# Preamp2_schematic.net
KiCad netlist of a schematic drawn in Altium Designer
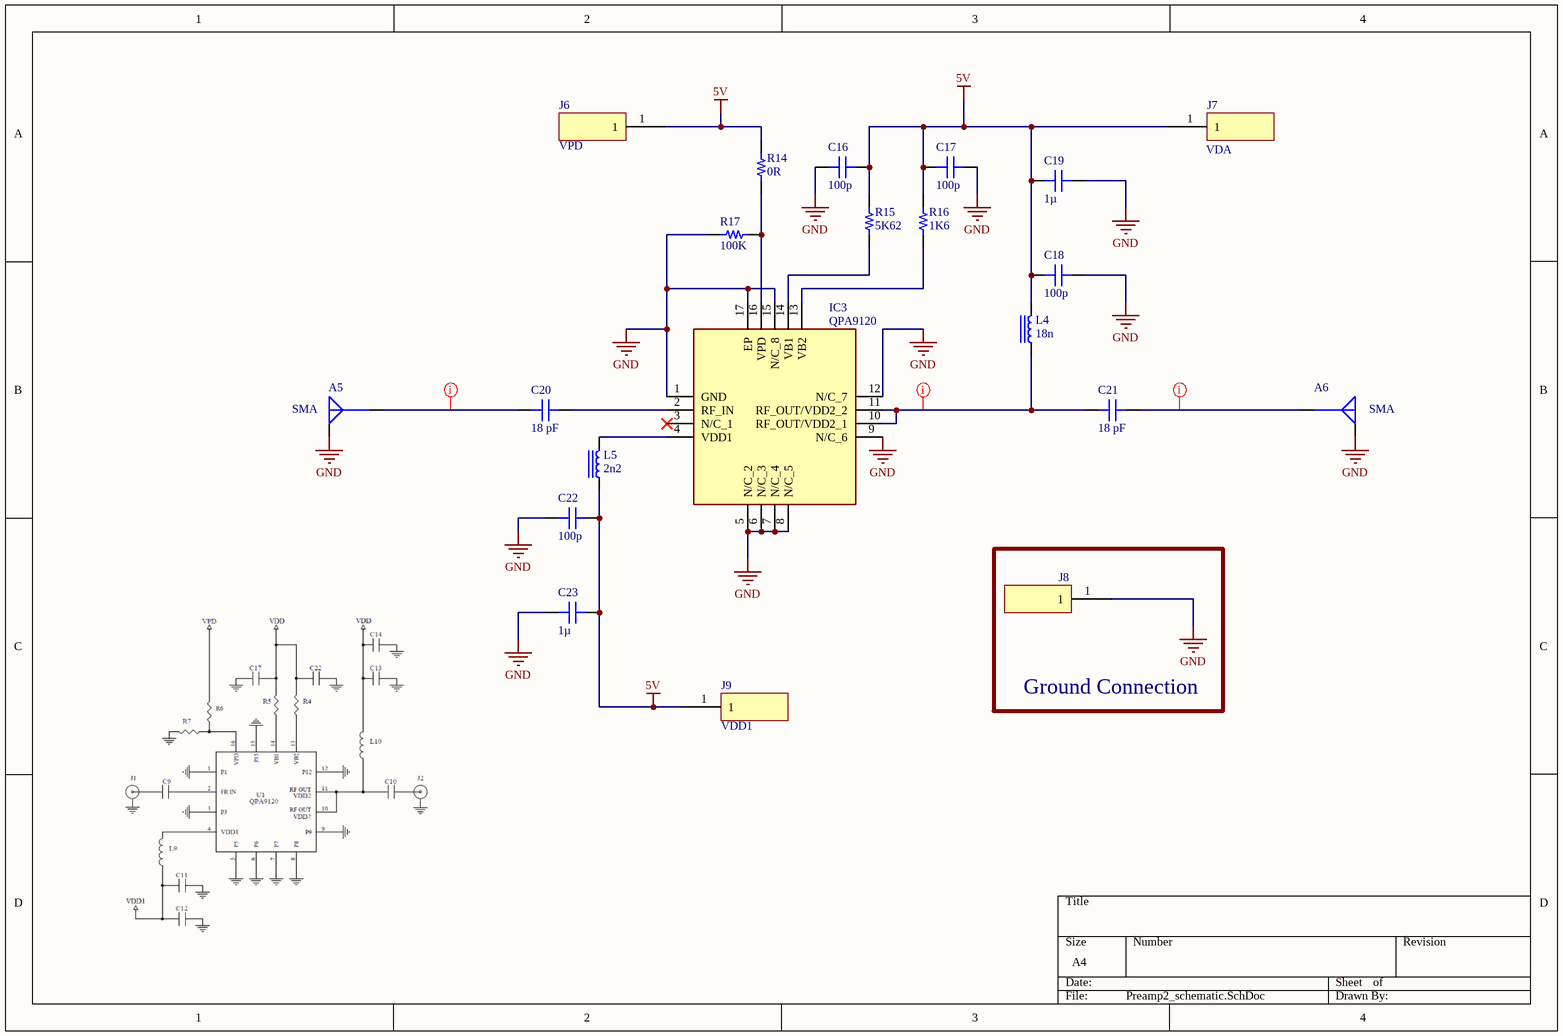
[diagram p0: Preamp2_schematic.SchDoc]

(export (version "E")
  (design (tool "Eeschema 10.0.6"))
  (components
    (comp (ref "A5")
      (value "0732511150")
      (footprint "MOLEX SD-73251-115")
      (description "CONN SMA RCPT STR 50OHM EDGE MNT")
      (fields (field (name "CONNECTOR STYLE") "SMA") (field (name "MANUFACTURER") "Molex"))
      (libsource (lib "Celestial Altium Library - altium_library") (part "Basic Antenna"))
    )
    (comp (ref "A6")
      (value "0732511150")
      (footprint "MOLEX SD-73251-115")
      (description "CONN SMA RCPT STR 50OHM EDGE MNT")
      (fields (field (name "CONNECTOR STYLE") "SMA") (field (name "MANUFACTURER") "Molex"))
      (libsource (lib "Celestial Altium Library - altium_library") (part "Basic Antenna"))
    )
    (comp (ref "C16")
      (value "100p")
      (footprint "CAP 0402_1005 RF")
      (description "CAP CER 100PF 25V C0G/NP0 0402")
      (fields (field (name "PART NUMBER") "CBR04C101J3GAC") (field (name "MANUFACTURER") "KEMET"))
      (libsource (lib "Celestial Altium Library - altium_library") (part "Capacitor"))
    )
    (comp (ref "C17")
      (value "100p")
      (footprint "CAP 0402_1005 RF")
      (description "CAP CER 100PF 25V C0G/NP0 0402")
      (fields (field (name "PART NUMBER") "CBR04C101J3GAC") (field (name "MANUFACTURER") "KEMET"))
      (libsource (lib "Celestial Altium Library - altium_library") (part "Capacitor"))
    )
    (comp (ref "C18")
      (value "100p")
      (footprint "CAP 0402_1005 RF")
      (description "CAP CER 100PF 25V C0G/NP0 0402")
      (fields (field (name "PART NUMBER") "CBR04C101J3GAC") (field (name "MANUFACTURER") "KEMET"))
      (libsource (lib "Celestial Altium Library - altium_library") (part "Capacitor"))
    )
    (comp (ref "C19")
      (value "1µ")
      (footprint "CAP 0603_1608")
      (description "CAP CER 1UF 25V X7R 0603")
      (fields
        (field (name "PART NUMBER") "GCM188R71E105KA64J")
        (field (name "MANUFACTURER") "Murata Electronics")
      )
      (libsource (lib "Celestial Altium Library - altium_library") (part "Capacitor"))
    )
    (comp (ref "C20")
      (value "18 pF")
      (footprint "CAP 0402_1005 RF")
      (description "CAP CER 18PF 200V NP0 0402")
      (fields
        (field (name "PART NUMBER") "600L180GT200T")
        (field (name "MANUFACTURER") "American Technical Ceramics")
      )
      (libsource (lib "Celestial Altium Library - altium_library") (part "Capacitor"))
    )
    (comp (ref "C21")
      (value "18 pF")
      (footprint "CAP 0402_1005 RF")
      (description "CAP CER 18PF 200V NP0 0402")
      (fields
        (field (name "PART NUMBER") "600L180GT200T")
        (field (name "MANUFACTURER") "American Technical Ceramics")
      )
      (libsource (lib "Celestial Altium Library - altium_library") (part "Capacitor"))
    )
    (comp (ref "C22")
      (value "100p")
      (footprint "CAP 0603_1608 RF")
      (description "CAP CER 100PF 250V NP0 0603")
      (fields
        (field (name "PART NUMBER") "600S101GW250XT")
        (field (name "MANUFACTURER") "American Technical Ceramics")
      )
      (libsource (lib "Celestial Altium Library - altium_library") (part "Capacitor"))
    )
    (comp (ref "C23")
      (value "1µ")
      (footprint "CAP 0603_1608")
      (description "CAP CER 1UF 25V X7R 0603")
      (fields
        (field (name "PART NUMBER") "GCM188R71E105KA64J")
        (field (name "MANUFACTURER") "Murata Electronics")
      )
      (libsource (lib "Celestial Altium Library - altium_library") (part "Capacitor"))
    )
    (comp (ref "IC3")
      (value "QPA9120")
      (footprint "SamacSys:QFN50P300X300X86-17N-D")
      (description "Integrated Circuit")
      (libsource (lib "SamacSys") (part "QPA9120"))
    )
    (comp (ref "J6")
      (value "Nail_Head")
      (footprint "Nail_Head")
      (description "1460-2-00-80-00-00-03-0 Mill-Max")
      (libsource (lib "") (part "Nail_Head_1"))
    )
    (comp (ref "J7")
      (value "Nail_Head")
      (footprint "Nail_Head")
      (description "1460-2-00-80-00-00-03-0 Mill-Max")
      (libsource (lib "ARIS_COM_Transponder") (part "Nail_Head"))
    )
    (comp (ref "J8")
      (value "Nail_Head")
      (footprint "Nail_Head")
      (description "1460-2-00-80-00-00-03-0 Mill-Max")
      (libsource (lib "") (part "Nail_Head_1"))
    )
    (comp (ref "J9")
      (value "Nail_Head")
      (footprint "Nail_Head")
      (description "1460-2-00-80-00-00-03-0 Mill-Max")
      (libsource (lib "ARIS_COM_Transponder") (part "Nail_Head"))
    )
    (comp (ref "L4")
      (value "18n")
      (footprint "IND 0402_1005 RF WW")
      (description "FIXED IND 18NH 1.05A 0.13OHM SMD")
      (fields
        (field (name "PART NUMBER") "LQW15AN18NG8ZD")
        (field (name "MANUFACTURER") "Murata Electronics")
      )
      (libsource (lib "Celestial Altium Library - altium_library") (part "Inductor"))
    )
    (comp (ref "L5")
      (value "2n2")
      (footprint "IND 0402_1005 RF WW")
      (description "FIXED IND 2.2NH 2.53A 0.022OHM")
      (fields
        (field (name "PART NUMBER") "LQW15AN2N2D8ZD")
        (field (name "MANUFACTURER") "Murata Electronics")
      )
      (libsource (lib "Celestial Altium Library - altium_library") (part "Inductor"))
    )
    (comp (ref "R14")
      (value "0R")
      (footprint "RES 0603_1608")
      (description "0603 26 AMP JUMPER")
      (fields (field (name "PART NUMBER") "JR0603X26E") (field (name "MANUFACTURER") "Ohmite"))
      (libsource (lib "Celestial Altium Library - altium_library") (part "Resistor"))
    )
    (comp (ref "R15")
      (value "5K62")
      (footprint "RES 0402_1005")
      (description "RES SMD 5.62K OHM 1% 1/16W 0402")
      (fields (field (name "PART NUMBER") "CRCW04025K62FKED") (field (name "MANUFACTURER") "Vishay Dale"))
      (libsource (lib "Celestial Altium Library - altium_library") (part "Resistor"))
    )
    (comp (ref "R16")
      (value "1K6")
      (footprint "RES 0402_1005")
      (description "RES SMD 1.6K OHM 1% 1/16W 0402")
      (fields (field (name "PART NUMBER") "CR0402-FX-1601GLF") (field (name "MANUFACTURER") "Bourns Inc."))
      (libsource (lib "Celestial Altium Library - altium_library") (part "Resistor"))
    )
    (comp (ref "R17")
      (value "100K")
      (footprint "RES 0402_1005")
      (description "RES SMD 100K OHM 1% 1/5W 0402")
      (fields (field (name "PART NUMBER") "CRCW0402100KFKEDHP") (field (name "MANUFACTURER") "Vishay Dale"))
      (libsource (lib "Celestial Altium Library - altium_library") (part "Resistor"))
    )
  )
  (nets
    (net (code "1") (name "5V") (class "Default")
      (node (ref "C16") (pin "2") (pinfunction "2_2") (pintype "passive"))
      (node (ref "C17") (pin "1") (pinfunction "1_1") (pintype "passive"))
      (node (ref "C18") (pin "1") (pinfunction "1_1") (pintype "passive"))
      (node (ref "C19") (pin "1") (pinfunction "1_1") (pintype "passive"))
      (node (ref "C22") (pin "2") (pinfunction "2_2") (pintype "passive"))
      (node (ref "C23") (pin "2") (pinfunction "2_2") (pintype "passive"))
      (node (ref "J6") (pin "1") (pinfunction "1_1") (pintype "passive"))
      (node (ref "J7") (pin "1") (pinfunction "1_1") (pintype "passive"))
      (node (ref "J9") (pin "1") (pinfunction "1_1") (pintype "passive"))
      (node (ref "L4") (pin "2") (pinfunction "2_2") (pintype "passive"))
      (node (ref "L5") (pin "1") (pinfunction "1_1") (pintype "passive"))
      (node (ref "R14") (pin "2") (pinfunction "2_2") (pintype "passive"))
      (node (ref "R15") (pin "2") (pinfunction "2_2") (pintype "passive"))
      (node (ref "R16") (pin "2") (pinfunction "2_2") (pintype "passive"))
    )
    (net (code "2") (name "GND") (class "Default")
      (node (ref "A5") (pin "G") (pinfunction "G_G") (pintype "passive"))
      (node (ref "A6") (pin "G") (pinfunction "G_G") (pintype "passive"))
      (node (ref "C16") (pin "1") (pinfunction "1_1") (pintype "passive"))
      (node (ref "C17") (pin "2") (pinfunction "2_2") (pintype "passive"))
      (node (ref "C18") (pin "2") (pinfunction "2_2") (pintype "passive"))
      (node (ref "C19") (pin "2") (pinfunction "2_2") (pintype "passive"))
      (node (ref "C22") (pin "1") (pinfunction "1_1") (pintype "passive"))
      (node (ref "C23") (pin "1") (pinfunction "1_1") (pintype "passive"))
      (node (ref "IC3") (pin "1") (pinfunction "GND_1") (pintype "passive"))
      (node (ref "IC3") (pin "12") (pinfunction "N/C_7_12") (pintype "passive"))
      (node (ref "IC3") (pin "15") (pinfunction "N/C_8_15") (pintype "passive"))
      (node (ref "IC3") (pin "17") (pinfunction "EP_17") (pintype "passive"))
      (node (ref "IC3") (pin "5") (pinfunction "N/C_2_5") (pintype "passive"))
      (node (ref "IC3") (pin "6") (pinfunction "N/C_3_6") (pintype "passive"))
      (node (ref "IC3") (pin "7") (pinfunction "N/C_4_7") (pintype "passive"))
      (node (ref "IC3") (pin "8") (pinfunction "N/C_5_8") (pintype "passive"))
      (node (ref "IC3") (pin "9") (pinfunction "N/C_6_9") (pintype "passive"))
      (node (ref "J8") (pin "1") (pinfunction "1_1") (pintype "passive"))
      (node (ref "R17") (pin "1") (pinfunction "1_1") (pintype "passive"))
    )
    (net (code "3") (name "Net-(A5-PadS)") (class "Default")
      (node (ref "A5") (pin "S") (pinfunction "S_S") (pintype "passive"))
      (node (ref "C20") (pin "1") (pinfunction "1_1") (pintype "passive"))
    )
    (net (code "4") (name "Net-(A6-PadS)") (class "Default")
      (node (ref "A6") (pin "S") (pinfunction "S_S") (pintype "passive"))
      (node (ref "C21") (pin "2") (pinfunction "2_2") (pintype "passive"))
    )
    (net (code "5") (name "Net-(IC3-RF_IN)") (class "Default")
      (node (ref "C20") (pin "2") (pinfunction "2_2") (pintype "passive"))
      (node (ref "IC3") (pin "2") (pinfunction "RF_IN_2") (pintype "passive"))
    )
    (net (code "6") (name "Net-(IC3-RF_OUT{slash}VDD2_1)") (class "Default")
      (node (ref "C21") (pin "1") (pinfunction "1_1") (pintype "passive"))
      (node (ref "IC3") (pin "10") (pinfunction "RF_OUT/VDD2_1_10") (pintype "passive"))
      (node (ref "IC3") (pin "11") (pinfunction "RF_OUT/VDD2_2_11") (pintype "passive"))
      (node (ref "L4") (pin "1") (pinfunction "1_1") (pintype "passive"))
    )
    (net (code "7") (name "Net-(IC3-VB1)") (class "Default")
      (node (ref "IC3") (pin "14") (pinfunction "VB1_14") (pintype "passive"))
      (node (ref "R15") (pin "1") (pinfunction "1_1") (pintype "passive"))
    )
    (net (code "8") (name "Net-(IC3-VB2)") (class "Default")
      (node (ref "IC3") (pin "13") (pinfunction "VB2_13") (pintype "passive"))
      (node (ref "R16") (pin "1") (pinfunction "1_1") (pintype "passive"))
    )
    (net (code "9") (name "Net-(IC3-VDD1)") (class "Default")
      (node (ref "IC3") (pin "4") (pinfunction "VDD1_4") (pintype "passive"))
      (node (ref "L5") (pin "2") (pinfunction "2_2") (pintype "passive"))
    )
    (net (code "10") (name "Net-(IC3-VPD)") (class "Default")
      (node (ref "IC3") (pin "16") (pinfunction "VPD_16") (pintype "passive"))
      (node (ref "R14") (pin "1") (pinfunction "1_1") (pintype "passive"))
      (node (ref "R17") (pin "2") (pinfunction "2_2") (pintype "passive"))
    )
    (net (code "11") (name "unconnected-(IC3-N{slash}C_1-Pad3)") (class "Default")
      (node (ref "IC3") (pin "3") (pinfunction "N/C_1_3") (pintype "passive+no_connect"))
    )
  )
)
